# FMU_FMU_REV_1B.net
KiCad netlist of a schematic drawn in Altium Designer
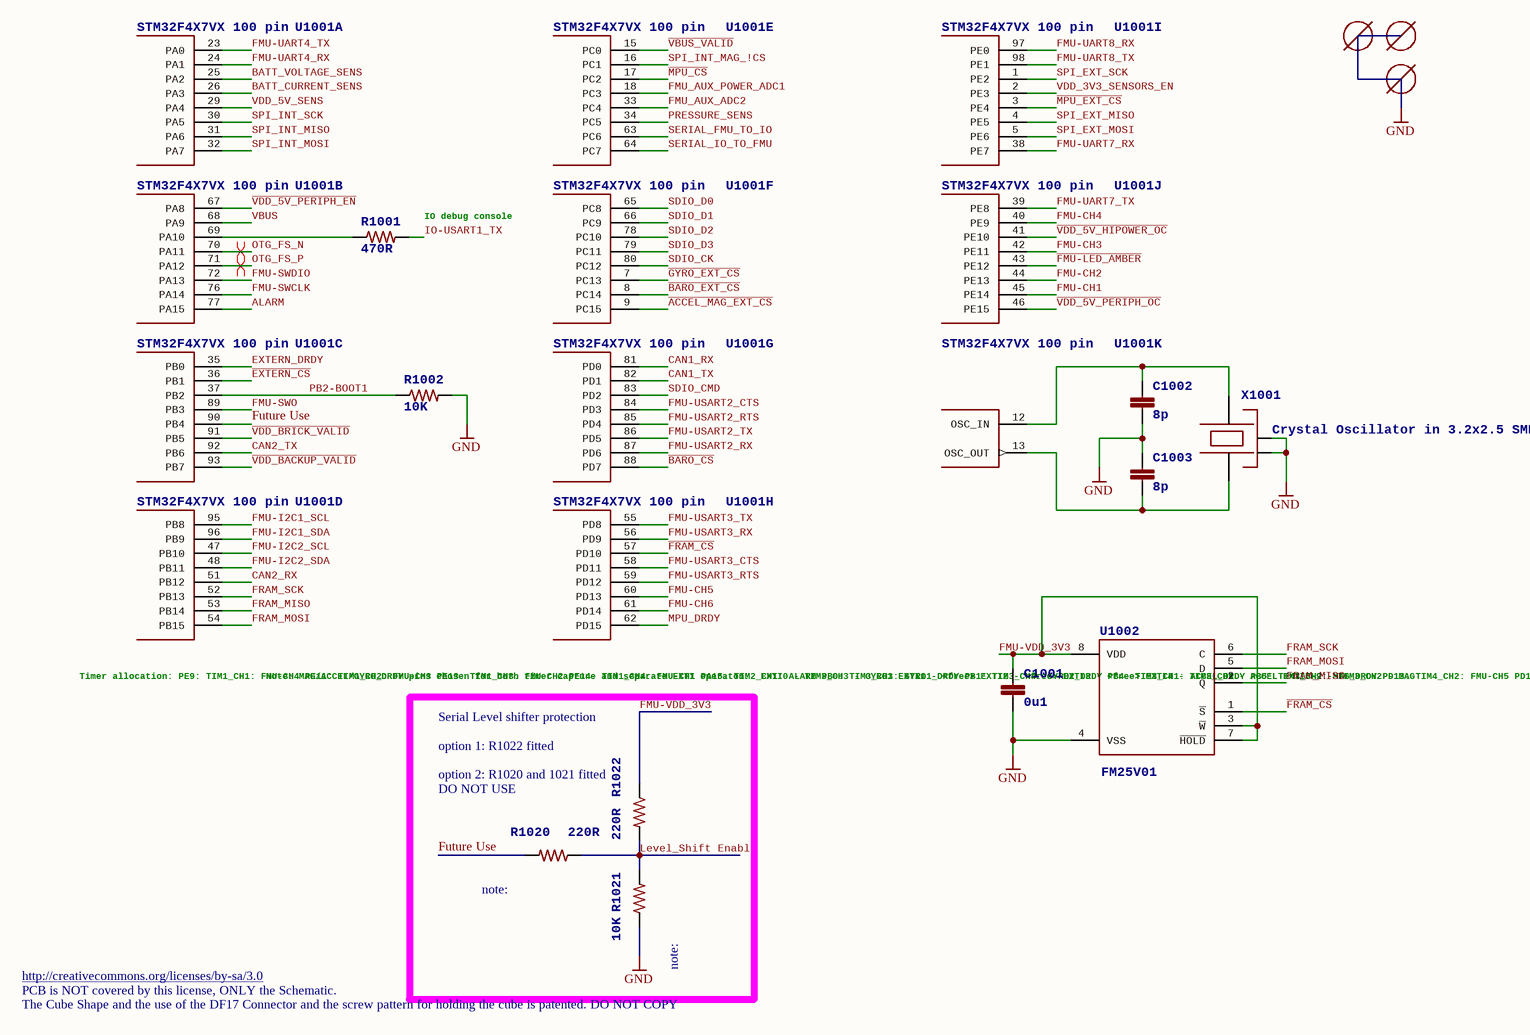
[diagram p0: FMU_FMU_REV_1B.SchDoc]

(export (version "E")
  (design (tool "Eeschema 10.0.6"))
  (components
    (comp (ref "C1001")
      (value "0u1")
      (footprint "0402-CAP")
      (description "CAP CER 0.1UF 16V Y5V 0402")
      (libsource (lib "pixhawk2") (part "CAP0402"))
    )
    (comp (ref "C1002")
      (value "8p")
      (footprint "0402-CAP")
      (description "CAP CER 8PF 50V C0G 0402")
      (libsource (lib "pixhawk2") (part "CAP0402"))
    )
    (comp (ref "C1003")
      (value "8p")
      (footprint "0402-CAP")
      (description "CAP CER 8PF 50V C0G 0402")
      (libsource (lib "pixhawk2") (part "CAP0402"))
    )
    (comp (ref "M3_MOUNT1001")
      (value "MOUNT-HOLE1.8MM")
      (footprint "MOUNT-HOLE1.8")
      (libsource (lib "pixhawk2") (part "MOUNT-HOLE1.8MM"))
    )
    (comp (ref "M3_MOUNT1003")
      (value "MOUNT-HOLE1.8MM")
      (footprint "MOUNT-HOLE1.8")
      (libsource (lib "pixhawk2") (part "MOUNT-HOLE1.8MM"))
    )
    (comp (ref "M3_MOUNT1004")
      (value "MOUNT-HOLE1.8MM")
      (footprint "MOUNT-HOLE1.8")
      (libsource (lib "pixhawk2") (part "MOUNT-HOLE1.8MM"))
    )
    (comp (ref "R1001")
      (value "470R")
      (footprint "0402-RES")
      (description "RES 470 OHM 1/16W 1% 0402 SMD")
      (libsource (lib "pixhawk2") (part "RESISTOR0402-RES"))
    )
    (comp (ref "R1002")
      (value "10K")
      (footprint "0402-RES")
      (description "RES 10K OHM 1/16W 1% 0402 SMD")
      (libsource (lib "pixhawk2") (part "RESISTOR0402-RES"))
    )
    (comp (ref "R1020")
      (value "220R")
      (footprint "0402-RES")
      (description "RES 220 OHM 1/16W 1% 0402 SMD")
      (libsource (lib "pixhawk2") (part "RESISTOR0402-RES"))
    )
    (comp (ref "R1021")
      (value "10K")
      (footprint "0402-RES")
      (description "RES 10K OHM 1/16W 1% 0402 SMD")
      (libsource (lib "pixhawk2") (part "RESISTOR0402-RES"))
    )
    (comp (ref "R1022")
      (value "220R")
      (footprint "0402-RES")
      (description "RES 220 OHM 1/16W 1% 0402 SMD")
      (libsource (lib "pixhawk2") (part "RESISTOR0402-RES"))
    )
    (comp (ref "U1001")
      (value "STM32F4X7VX 100 pin")
      (footprint "TQFP100")
      (description "REV 3 Silicon or later IC MCU ARM 2MB FLASH 100LQFP")
      (libsource (lib "pixhawk2") (part "STM32F4X7VX"))
    )
    (comp (ref "U1002")
      (value "FM25V01")
      (footprint "SO08")
      (description "IC FRAM 128KBIT 40MHZ 8SOIC")
      (libsource (lib "pixhawk2") (part "FM25V01"))
    )
    (comp (ref "X1001")
      (value "Crystal Oscillator in 3.2x2.5 SMD")
      (footprint "OSCILLATOR-3.2X2.5")
      (description "CRYSTAL 24MHZ 8PF SMD")
      (libsource (lib "pixhawk2") (part "OSCILLATOR-3.2X2.5"))
    )
  )
  (nets
    (net (code "1") (name "/ALARM") (class "Default")
      (node (ref "U1001") (pin "77") (pinfunction "PA15_77") (pintype "passive"))
    )
    (net (code "2") (name "/BATT_CURRENT_SENS") (class "Default")
      (node (ref "U1001") (pin "26") (pinfunction "PA3_26") (pintype "passive"))
    )
    (net (code "3") (name "/BATT_VOLTAGE_SENS") (class "Default")
      (node (ref "U1001") (pin "25") (pinfunction "PA2_25") (pintype "passive"))
    )
    (net (code "4") (name "/CAN1_RX") (class "Default")
      (node (ref "U1001") (pin "81") (pinfunction "PD0_81") (pintype "passive"))
    )
    (net (code "5") (name "/CAN1_TX") (class "Default")
      (node (ref "U1001") (pin "82") (pinfunction "PD1_82") (pintype "passive"))
    )
    (net (code "6") (name "/CAN2_RX") (class "Default")
      (node (ref "U1001") (pin "51") (pinfunction "PB12_51") (pintype "passive"))
    )
    (net (code "7") (name "/CAN2_TX") (class "Default")
      (node (ref "U1001") (pin "92") (pinfunction "PB6_92") (pintype "passive"))
    )
    (net (code "8") (name "/EXTERN_DRDY") (class "Default")
      (node (ref "U1001") (pin "35") (pinfunction "PB0_35") (pintype "passive"))
    )
    (net (code "9") (name "/FMU-CH1") (class "Default")
      (node (ref "U1001") (pin "45") (pinfunction "PE14_45") (pintype "passive"))
    )
    (net (code "10") (name "/FMU-CH2") (class "Default")
      (node (ref "U1001") (pin "44") (pinfunction "PE13_44") (pintype "passive"))
    )
    (net (code "11") (name "/FMU-CH3") (class "Default")
      (node (ref "U1001") (pin "42") (pinfunction "PE11_42") (pintype "passive"))
    )
    (net (code "12") (name "/FMU-CH4") (class "Default")
      (node (ref "U1001") (pin "40") (pinfunction "PE9_40") (pintype "passive"))
    )
    (net (code "13") (name "/FMU-CH5") (class "Default")
      (node (ref "U1001") (pin "60") (pinfunction "PD13_60") (pintype "passive"))
    )
    (net (code "14") (name "/FMU-CH6") (class "Default")
      (node (ref "U1001") (pin "61") (pinfunction "PD14_61") (pintype "passive"))
    )
    (net (code "15") (name "/FMU-I2C1_SCL") (class "Default")
      (node (ref "U1001") (pin "95") (pinfunction "PB8_95") (pintype "passive"))
    )
    (net (code "16") (name "/FMU-I2C1_SDA") (class "Default")
      (node (ref "U1001") (pin "96") (pinfunction "PB9_96") (pintype "passive"))
    )
    (net (code "17") (name "/FMU-I2C2_SCL") (class "Default")
      (node (ref "U1001") (pin "47") (pinfunction "PB10_47") (pintype "passive"))
    )
    (net (code "18") (name "/FMU-I2C2_SDA") (class "Default")
      (node (ref "U1001") (pin "48") (pinfunction "PB11_48") (pintype "passive"))
    )
    (net (code "19") (name "/FMU-SWCLK") (class "Default")
      (node (ref "U1001") (pin "76") (pinfunction "PA14_76") (pintype "passive"))
    )
    (net (code "20") (name "/FMU-SWDIO") (class "Default")
      (node (ref "U1001") (pin "72") (pinfunction "PA13_72") (pintype "passive"))
    )
    (net (code "21") (name "/FMU-SWO") (class "Default")
      (node (ref "U1001") (pin "89") (pinfunction "PB3_89") (pintype "passive"))
    )
    (net (code "22") (name "/FMU-UART4_RX") (class "Default")
      (node (ref "U1001") (pin "24") (pinfunction "PA1_24") (pintype "passive"))
    )
    (net (code "23") (name "/FMU-UART4_TX") (class "Default")
      (node (ref "U1001") (pin "23") (pinfunction "PA0_23") (pintype "passive"))
    )
    (net (code "24") (name "/FMU-UART7_RX") (class "Default")
      (node (ref "U1001") (pin "38") (pinfunction "PE7_38") (pintype "passive"))
    )
    (net (code "25") (name "/FMU-UART7_TX") (class "Default")
      (node (ref "U1001") (pin "39") (pinfunction "PE8_39") (pintype "passive"))
    )
    (net (code "26") (name "/FMU-UART8_RX") (class "Default")
      (node (ref "U1001") (pin "97") (pinfunction "PE0_97") (pintype "passive"))
    )
    (net (code "27") (name "/FMU-UART8_TX") (class "Default")
      (node (ref "U1001") (pin "98") (pinfunction "PE1_98") (pintype "passive"))
    )
    (net (code "28") (name "/FMU-USART2_CTS") (class "Default")
      (node (ref "U1001") (pin "84") (pinfunction "PD3_84") (pintype "passive"))
    )
    (net (code "29") (name "/FMU-USART2_RTS") (class "Default")
      (node (ref "U1001") (pin "85") (pinfunction "PD4_85") (pintype "passive"))
    )
    (net (code "30") (name "/FMU-USART2_RX") (class "Default")
      (node (ref "U1001") (pin "87") (pinfunction "PD6_87") (pintype "passive"))
    )
    (net (code "31") (name "/FMU-USART2_TX") (class "Default")
      (node (ref "U1001") (pin "86") (pinfunction "PD5_86") (pintype "passive"))
    )
    (net (code "32") (name "/FMU-USART3_CTS") (class "Default")
      (node (ref "U1001") (pin "58") (pinfunction "PD11_58") (pintype "passive"))
    )
    (net (code "33") (name "/FMU-USART3_RTS") (class "Default")
      (node (ref "U1001") (pin "59") (pinfunction "PD12_59") (pintype "passive"))
    )
    (net (code "34") (name "/FMU-USART3_RX") (class "Default")
      (node (ref "U1001") (pin "56") (pinfunction "PD9_56") (pintype "passive"))
    )
    (net (code "35") (name "/FMU-USART3_TX") (class "Default")
      (node (ref "U1001") (pin "55") (pinfunction "PD8_55") (pintype "passive"))
    )
    (net (code "36") (name "/FMU-VDD_3V3") (class "Default")
      (node (ref "C1001") (pin "P$1") (pinfunction "1_P$1") (pintype "passive"))
      (node (ref "R1022") (pin "P$1") (pinfunction "1_P$1") (pintype "passive"))
      (node (ref "U1002") (pin "3") (pinfunction "~{W}_3") (pintype "passive"))
      (node (ref "U1002") (pin "7") (pinfunction "~{HOLD}_7") (pintype "passive"))
      (node (ref "U1002") (pin "8") (pinfunction "VDD_8") (pintype "passive"))
    )
    (net (code "37") (name "/FMU_AUX_ADC2") (class "Default")
      (node (ref "U1001") (pin "33") (pinfunction "PC4_33") (pintype "passive"))
    )
    (net (code "38") (name "/FMU_AUX_POWER_ADC1") (class "Default")
      (node (ref "U1001") (pin "18") (pinfunction "PC3_18") (pintype "passive"))
    )
    (net (code "39") (name "/FRAM_MISO") (class "Default")
      (node (ref "U1001") (pin "53") (pinfunction "PB14_53") (pintype "passive"))
      (node (ref "U1002") (pin "2") (pinfunction "Q_2") (pintype "passive"))
    )
    (net (code "40") (name "/FRAM_MOSI") (class "Default")
      (node (ref "U1001") (pin "54") (pinfunction "PB15_54") (pintype "passive"))
      (node (ref "U1002") (pin "5") (pinfunction "D_5") (pintype "passive"))
    )
    (net (code "41") (name "/FRAM_SCK") (class "Default")
      (node (ref "U1001") (pin "52") (pinfunction "PB13_52") (pintype "passive"))
      (node (ref "U1002") (pin "6") (pinfunction "C_6") (pintype "passive"))
    )
    (net (code "42") (name "/Future Use") (class "Default")
      (node (ref "R1020") (pin "P$2") (pinfunction "2_P$2") (pintype "passive"))
      (node (ref "U1001") (pin "90") (pinfunction "PB4_90") (pintype "passive"))
    )
    (net (code "43") (name "/IO-USART1_TX") (class "Default")
      (node (ref "R1001") (pin "P$2") (pinfunction "2_P$2") (pintype "passive"))
    )
    (net (code "44") (name "/Level_Shift Enable") (class "Default")
      (node (ref "R1020") (pin "P$1") (pinfunction "1_P$1") (pintype "passive"))
      (node (ref "R1021") (pin "P$2") (pinfunction "2_P$2") (pintype "passive"))
      (node (ref "R1022") (pin "P$2") (pinfunction "2_P$2") (pintype "passive"))
    )
    (net (code "45") (name "/MPU_DRDY") (class "Default")
      (node (ref "U1001") (pin "62") (pinfunction "PD15_62") (pintype "passive"))
    )
    (net (code "46") (name "/OTG_FS_N") (class "Default")
      (node (ref "U1001") (pin "70") (pinfunction "PA11_70") (pintype "passive"))
    )
    (net (code "47") (name "/OTG_FS_P") (class "Default")
      (node (ref "U1001") (pin "71") (pinfunction "PA12_71") (pintype "passive"))
    )
    (net (code "48") (name "/PB2-BOOT1") (class "Default")
      (node (ref "R1002") (pin "P$1") (pinfunction "1_P$1") (pintype "passive"))
      (node (ref "U1001") (pin "37") (pinfunction "PB2_37") (pintype "passive"))
    )
    (net (code "49") (name "/PRESSURE_SENS") (class "Default")
      (node (ref "U1001") (pin "34") (pinfunction "PC5_34") (pintype "passive"))
    )
    (net (code "50") (name "/SDIO_CK") (class "Default")
      (node (ref "U1001") (pin "80") (pinfunction "PC12_80") (pintype "passive"))
    )
    (net (code "51") (name "/SDIO_CMD") (class "Default")
      (node (ref "U1001") (pin "83") (pinfunction "PD2_83") (pintype "passive"))
    )
    (net (code "52") (name "/SDIO_D0") (class "Default")
      (node (ref "U1001") (pin "65") (pinfunction "PC8_65") (pintype "passive"))
    )
    (net (code "53") (name "/SDIO_D1") (class "Default")
      (node (ref "U1001") (pin "66") (pinfunction "PC9_66") (pintype "passive"))
    )
    (net (code "54") (name "/SDIO_D2") (class "Default")
      (node (ref "U1001") (pin "78") (pinfunction "PC10_78") (pintype "passive"))
    )
    (net (code "55") (name "/SDIO_D3") (class "Default")
      (node (ref "U1001") (pin "79") (pinfunction "PC11_79") (pintype "passive"))
    )
    (net (code "56") (name "/SERIAL_FMU_TO_IO") (class "Default")
      (node (ref "U1001") (pin "63") (pinfunction "PC6_63") (pintype "passive"))
    )
    (net (code "57") (name "/SERIAL_IO_TO_FMU") (class "Default")
      (node (ref "U1001") (pin "64") (pinfunction "PC7_64") (pintype "passive"))
    )
    (net (code "58") (name "/SPI_EXT_MISO") (class "Default")
      (node (ref "U1001") (pin "4") (pinfunction "PE5_4") (pintype "passive"))
    )
    (net (code "59") (name "/SPI_EXT_MOSI") (class "Default")
      (node (ref "U1001") (pin "5") (pinfunction "PE6_5") (pintype "passive"))
    )
    (net (code "60") (name "/SPI_EXT_SCK") (class "Default")
      (node (ref "U1001") (pin "1") (pinfunction "PE2_1") (pintype "passive"))
    )
    (net (code "61") (name "/SPI_INT_MAG_!CS") (class "Default")
      (node (ref "U1001") (pin "16") (pinfunction "PC1_16") (pintype "passive"))
    )
    (net (code "62") (name "/SPI_INT_MISO") (class "Default")
      (node (ref "U1001") (pin "31") (pinfunction "PA6_31") (pintype "passive"))
    )
    (net (code "63") (name "/SPI_INT_MOSI") (class "Default")
      (node (ref "U1001") (pin "32") (pinfunction "PA7_32") (pintype "passive"))
    )
    (net (code "64") (name "/SPI_INT_SCK") (class "Default")
      (node (ref "U1001") (pin "30") (pinfunction "PA5_30") (pintype "passive"))
    )
    (net (code "65") (name "/VBUS") (class "Default")
      (node (ref "U1001") (pin "68") (pinfunction "PA9_68") (pintype "passive"))
    )
    (net (code "66") (name "/VDD_3V3_SENSORS_EN") (class "Default")
      (node (ref "U1001") (pin "2") (pinfunction "PE3_2") (pintype "passive"))
    )
    (net (code "67") (name "/VDD_5V_SENS") (class "Default")
      (node (ref "U1001") (pin "29") (pinfunction "PA4_29") (pintype "passive"))
    )
    (net (code "68") (name "/~{ACCEL_MAG_EXT_CS}") (class "Default")
      (node (ref "U1001") (pin "9") (pinfunction "PC15_9") (pintype "passive"))
    )
    (net (code "69") (name "/~{BARO_CS}") (class "Default")
      (node (ref "U1001") (pin "88") (pinfunction "PD7_88") (pintype "passive"))
    )
    (net (code "70") (name "/~{BARO_EXT_CS}") (class "Default")
      (node (ref "U1001") (pin "8") (pinfunction "PC14_8") (pintype "passive"))
    )
    (net (code "71") (name "/~{EXTERN_CS}") (class "Default")
      (node (ref "U1001") (pin "36") (pinfunction "PB1_36") (pintype "passive"))
    )
    (net (code "72") (name "/~{FMU-LED_AMBER}") (class "Default")
      (node (ref "U1001") (pin "43") (pinfunction "PE12_43") (pintype "passive"))
    )
    (net (code "73") (name "/~{FRAM_CS}") (class "Default")
      (node (ref "U1001") (pin "57") (pinfunction "PD10_57") (pintype "passive"))
      (node (ref "U1002") (pin "1") (pinfunction "~{S}_1") (pintype "passive"))
    )
    (net (code "74") (name "/~{GYRO_EXT_CS}") (class "Default")
      (node (ref "U1001") (pin "7") (pinfunction "PC13_7") (pintype "passive"))
    )
    (net (code "75") (name "/~{MPU_CS}") (class "Default")
      (node (ref "U1001") (pin "17") (pinfunction "PC2_17") (pintype "passive"))
    )
    (net (code "76") (name "/~{MPU_EXT_CS}") (class "Default")
      (node (ref "U1001") (pin "3") (pinfunction "PE4_3") (pintype "passive"))
    )
    (net (code "77") (name "/~{VBUS_VALID}") (class "Default")
      (node (ref "U1001") (pin "15") (pinfunction "PC0_15") (pintype "passive"))
    )
    (net (code "78") (name "/~{VDD_5V_HIPOWER_OC}") (class "Default")
      (node (ref "U1001") (pin "41") (pinfunction "PE10_41") (pintype "passive"))
    )
    (net (code "79") (name "/~{VDD_5V_PERIPH_EN}") (class "Default")
      (node (ref "U1001") (pin "67") (pinfunction "PA8_67") (pintype "passive"))
    )
    (net (code "80") (name "/~{VDD_5V_PERIPH_OC}") (class "Default")
      (node (ref "U1001") (pin "46") (pinfunction "PE15_46") (pintype "passive"))
    )
    (net (code "81") (name "/~{VDD_BACKUP_VALID}") (class "Default")
      (node (ref "U1001") (pin "93") (pinfunction "PB7_93") (pintype "passive"))
    )
    (net (code "82") (name "/~{VDD_BRICK_VALID}") (class "Default")
      (node (ref "U1001") (pin "91") (pinfunction "PB5_91") (pintype "passive"))
    )
    (net (code "83") (name "GND") (class "Default")
      (node (ref "C1001") (pin "P$2") (pinfunction "2_P$2") (pintype "passive"))
      (node (ref "C1002") (pin "P$2") (pinfunction "2_P$2") (pintype "passive"))
      (node (ref "C1003") (pin "P$1") (pinfunction "1_P$1") (pintype "passive"))
      (node (ref "R1002") (pin "P$2") (pinfunction "2_P$2") (pintype "passive"))
      (node (ref "R1021") (pin "P$1") (pinfunction "1_P$1") (pintype "passive"))
      (node (ref "U1002") (pin "4") (pinfunction "VSS_4") (pintype "passive"))
      (node (ref "X1001") (pin "2") (pinfunction "NC_2_2") (pintype "open_emitter"))
      (node (ref "X1001") (pin "4") (pinfunction "NC_4_4") (pintype "open_emitter"))
    )
    (net (code "84") (name "Net-(C1002-1)") (class "Default")
      (node (ref "C1002") (pin "P$1") (pinfunction "1_P$1") (pintype "passive"))
      (node (ref "U1001") (pin "12") (pinfunction "OSC_IN_12") (pintype "passive"))
      (node (ref "X1001") (pin "3") (pinfunction "3_3") (pintype "passive"))
    )
    (net (code "85") (name "Net-(C1003-2)") (class "Default")
      (node (ref "C1003") (pin "P$2") (pinfunction "2_P$2") (pintype "passive"))
      (node (ref "U1001") (pin "13") (pinfunction "OSC_OUT_13") (pintype "output"))
      (node (ref "X1001") (pin "1") (pinfunction "1_1") (pintype "passive"))
    )
    (net (code "86") (name "Net-(R1001-1)") (class "Default")
      (node (ref "R1001") (pin "P$1") (pinfunction "1_P$1") (pintype "passive"))
      (node (ref "U1001") (pin "69") (pinfunction "PA10_69") (pintype "passive"))
    )
  )
)
